# 6_upstream_con.net
KiCad netlist of a schematic drawn in Altium Designer
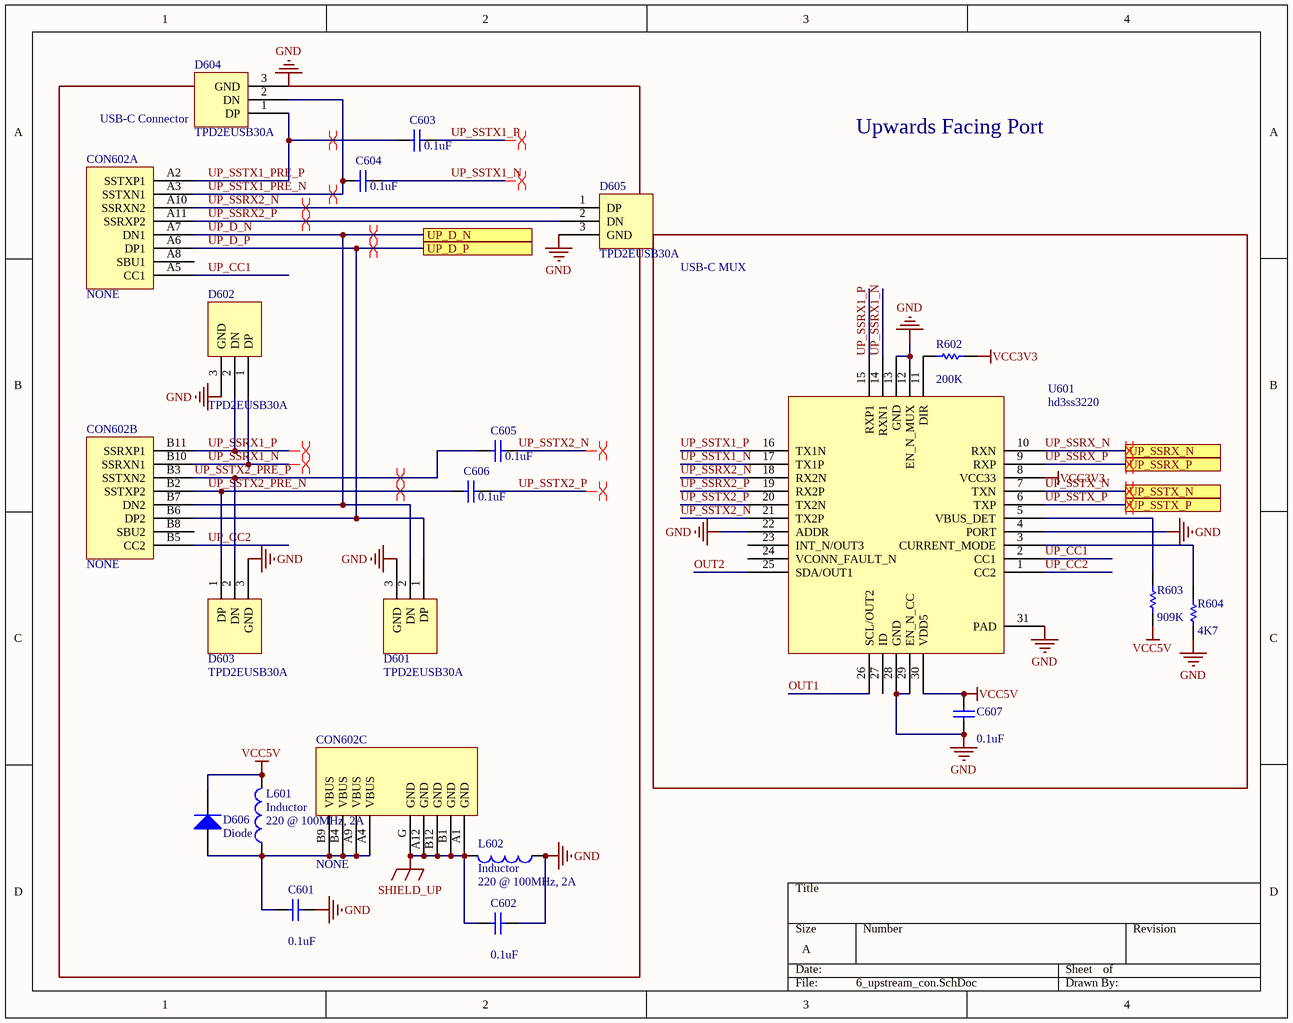
[diagram p0: 6_upstream_con.SchDoc]

(export (version "E")
  (design (tool "Eeschema 10.0.6"))
  (components
    (comp (ref "C601")
      (value "0.1uF")
      (footprint "C0603[1608]")
      (description "Capacitor")
      (fields (field (name "MFG") "KEMET") (field (name "LCSC PART #") "C14663"))
      (libsource (lib "Miscellaneous Devices") (part "Cap"))
    )
    (comp (ref "C602")
      (value "0.1uF")
      (footprint "C0603[1608]")
      (description "Capacitor")
      (fields (field (name "MFG") "KEMET") (field (name "LCSC PART #") "C14663"))
      (libsource (lib "Miscellaneous Devices") (part "Cap"))
    )
    (comp (ref "C603")
      (value "0.1uF")
      (footprint "C0402[1005]")
      (description "Capacitor")
      (fields (field (name "MFG") "KEMET") (field (name "LCSC PART #") "C1525"))
      (libsource (lib "Miscellaneous Devices") (part "Cap"))
    )
    (comp (ref "C604")
      (value "0.1uF")
      (footprint "C0402[1005]")
      (description "Capacitor")
      (fields (field (name "MFG") "KEMET") (field (name "LCSC PART #") "C1525"))
      (libsource (lib "Miscellaneous Devices") (part "Cap"))
    )
    (comp (ref "C605")
      (value "0.1uF")
      (footprint "C0402[1005]")
      (description "Capacitor")
      (fields (field (name "MFG") "KEMET") (field (name "LCSC PART #") "C1525"))
      (libsource (lib "Miscellaneous Devices") (part "Cap"))
    )
    (comp (ref "C606")
      (value "0.1uF")
      (footprint "C0402[1005]")
      (description "Capacitor")
      (fields (field (name "MFG") "KEMET") (field (name "LCSC PART #") "C1525"))
      (libsource (lib "Miscellaneous Devices") (part "Cap"))
    )
    (comp (ref "C607")
      (value "0.1uF")
      (footprint "C0603[1608]")
      (description "Capacitor")
      (fields (field (name "MFG") "KEMET") (field (name "LCSC PART #") "C14663"))
      (libsource (lib "Miscellaneous Devices") (part "Cap"))
    )
    (comp (ref "CON602")
      (value "for up to 1.6mm pcb")
      (footprint "XKB USB-C u262-241n-4bv64")
      (fields
        (field (name "JLC") "NONE")
        (field (name "LCSC PART #") "C388660")
        (field (name "MRF.PART") "U262-241N-4BV64")
      )
      (libsource (lib "") (part "XKB USB-C u262-241n-4bv64_1"))
    )
    (comp (ref "D601")
      (value "TPD2EUSB30A")
      (footprint "TPD2EUSB30A")
      (fields
        (field (name "MFG") "Texas Instruments")
        (field (name "LCSC PART #") "C94934")
        (field (name "MRF.PART") "TPD2EUSB30ADRTR")
      )
      (libsource (lib "") (part "TPD2EUSB30A_2"))
    )
    (comp (ref "D602")
      (value "TPD2EUSB30A")
      (footprint "TPD2EUSB30A")
      (fields
        (field (name "MFG") "Texas Instruments")
        (field (name "LCSC PART #") "C94934")
        (field (name "MRF.PART") "TPD2EUSB30ADRTR")
      )
      (libsource (lib "lib") (part "TPD2EUSB30A"))
    )
    (comp (ref "D603")
      (value "TPD2EUSB30A")
      (footprint "TPD2EUSB30A")
      (fields
        (field (name "MFG") "Texas Instruments")
        (field (name "LCSC PART #") "C94934")
        (field (name "MRF.PART") "TPD2EUSB30ADRTR")
      )
      (libsource (lib "") (part "TPD2EUSB30A_1"))
    )
    (comp (ref "D604")
      (value "TPD2EUSB30A")
      (footprint "TPD2EUSB30A")
      (fields
        (field (name "MFG") "Texas Instruments")
        (field (name "LCSC PART #") "C94934")
        (field (name "MRF.PART") "TPD2EUSB30ADRTR")
      )
      (libsource (lib "") (part "TPD2EUSB30A_1"))
    )
    (comp (ref "D605")
      (value "TPD2EUSB30A")
      (footprint "TPD2EUSB30A")
      (fields
        (field (name "MFG") "Texas Instruments")
        (field (name "LCSC PART #") "C94934")
        (field (name "MRF.PART") "TPD2EUSB30ADRTR")
      )
      (libsource (lib "lib") (part "TPD2EUSB30A"))
    )
    (comp (ref "D606")
      (value "Diode")
      (footprint "LED0603[1608]")
      (description "Default Diode")
      (fields (field (name "MFG") "Comchip Technology"))
      (libsource (lib "Miscellaneous Devices") (part "Diode"))
    )
    (comp (ref "L601")
      (value "Inductor")
      (footprint "L0603[1608]")
      (fields
        (field (name "ALTIUM_VALUE") "220 @ 100MHz, 2A")
        (field (name "MFG") "Murata Electronics North America")
        (field (name "LCSC PART #") "C85832")
        (field (name "MRF.PART") "BLM18KG331SN1D")
      )
      (libsource (lib "Miscellaneous Devices") (part "Inductor"))
    )
    (comp (ref "L602")
      (value "Inductor")
      (footprint "L0603[1608]")
      (fields
        (field (name "ALTIUM_VALUE") "220 @ 100MHz, 2A")
        (field (name "MFG") "Murata Electronics North America")
        (field (name "LCSC PART #") "C85832")
        (field (name "MRF.PART") "BLM18KG331SN1D")
      )
      (libsource (lib "Miscellaneous Devices") (part "Inductor"))
    )
    (comp (ref "R602")
      (value "200K")
      (footprint "R0603[1608]")
      (description "Resistor")
      (fields (field (name "MFG") "Vishay Dale") (field (name "LCSC PART #") "C25811"))
      (libsource (lib "Miscellaneous Devices") (part "Res1"))
    )
    (comp (ref "R603")
      (value "909K")
      (footprint "R0603[1608]")
      (description "Resistor")
      (fields (field (name "MFG") "Vishay Dale") (field (name "LCSC PART #") "C22935"))
      (libsource (lib "Miscellaneous Devices") (part "Res1"))
    )
    (comp (ref "R604")
      (value "4K7")
      (footprint "R0603[1608]")
      (description "Resistor")
      (fields (field (name "MFG") "Vishay Dale") (field (name "LCSC PART #") "C23162"))
      (libsource (lib "Miscellaneous Devices") (part "Res1"))
    )
    (comp (ref "U601")
      (value "hd3ss3220")
      (footprint "hd3ss3220")
      (fields
        (field (name "MFG") "Texas Instruments")
        (field (name "LCSC PART #") "C165155")
        (field (name "MRF.PART") "HD3SS3220RNHR")
      )
      (libsource (lib "lib") (part "hd3ss3220"))
    )
  )
  (nets
    (net (code "1") (name "/OUT1") (class "Default")
      (node (ref "U601") (pin "26") (pinfunction "SCL/OUT2_26") (pintype "passive"))
    )
    (net (code "2") (name "/OUT2") (class "Default")
      (node (ref "U601") (pin "25") (pinfunction "SDA/OUT1_25") (pintype "passive"))
    )
    (net (code "3") (name "/UP_CC1") (class "Default")
      (node (ref "CON602") (pin "A5") (pinfunction "CC1_A5") (pintype "passive"))
      (node (ref "U601") (pin "2") (pinfunction "CC1_2") (pintype "passive"))
    )
    (net (code "4") (name "/UP_CC2") (class "Default")
      (node (ref "CON602") (pin "B5") (pinfunction "CC2_B5") (pintype "passive"))
      (node (ref "U601") (pin "1") (pinfunction "CC2_1") (pintype "passive"))
    )
    (net (code "5") (name "/UP_D_N") (class "Default")
      (node (ref "CON602") (pin "A7") (pinfunction "DN1_A7") (pintype "passive"))
      (node (ref "CON602") (pin "B7") (pinfunction "DN2_B7") (pintype "passive"))
      (node (ref "D601") (pin "2") (pinfunction "DN_2") (pintype "passive"))
    )
    (net (code "6") (name "/UP_D_P") (class "Default")
      (node (ref "CON602") (pin "A6") (pinfunction "DP1_A6") (pintype "passive"))
      (node (ref "CON602") (pin "B6") (pinfunction "DP2_B6") (pintype "passive"))
      (node (ref "D601") (pin "1") (pinfunction "DP_1") (pintype "passive"))
    )
    (net (code "7") (name "/UP_SSRX1_N") (class "Default")
      (node (ref "CON602") (pin "B10") (pinfunction "SSRXN1_B10") (pintype "passive"))
      (node (ref "D602") (pin "1") (pinfunction "DP_1") (pintype "passive"))
      (node (ref "U601") (pin "14") (pinfunction "RXN1_14") (pintype "passive"))
    )
    (net (code "8") (name "/UP_SSRX1_P") (class "Default")
      (node (ref "CON602") (pin "B11") (pinfunction "SSRXP1_B11") (pintype "passive"))
      (node (ref "D602") (pin "2") (pinfunction "DN_2") (pintype "passive"))
      (node (ref "U601") (pin "15") (pinfunction "RXP1_15") (pintype "passive"))
    )
    (net (code "9") (name "/UP_SSRX2_N") (class "Default")
      (node (ref "CON602") (pin "A10") (pinfunction "SSRXN2_A10") (pintype "passive"))
      (node (ref "D605") (pin "1") (pinfunction "DP_1") (pintype "passive"))
      (node (ref "U601") (pin "18") (pinfunction "RX2N_18") (pintype "passive"))
    )
    (net (code "10") (name "/UP_SSRX2_P") (class "Default")
      (node (ref "CON602") (pin "A11") (pinfunction "SSRXP2_A11") (pintype "passive"))
      (node (ref "D605") (pin "2") (pinfunction "DN_2") (pintype "passive"))
      (node (ref "U601") (pin "19") (pinfunction "RX2P_19") (pintype "passive"))
    )
    (net (code "11") (name "/UP_SSRX_N") (class "Default")
      (node (ref "U601") (pin "10") (pinfunction "RXN_10") (pintype "passive"))
    )
    (net (code "12") (name "/UP_SSRX_P") (class "Default")
      (node (ref "U601") (pin "9") (pinfunction "RXP_9") (pintype "passive"))
    )
    (net (code "13") (name "/UP_SSTX1_N") (class "Default")
      (node (ref "C604") (pin "2") (pinfunction "2_2") (pintype "passive"))
      (node (ref "U601") (pin "17") (pinfunction "TX1P_17") (pintype "passive"))
    )
    (net (code "14") (name "/UP_SSTX1_P") (class "Default")
      (node (ref "C603") (pin "2") (pinfunction "2_2") (pintype "passive"))
      (node (ref "U601") (pin "16") (pinfunction "TX1N_16") (pintype "passive"))
    )
    (net (code "15") (name "/UP_SSTX1_PRE_N") (class "Default")
      (node (ref "C604") (pin "1") (pinfunction "1_1") (pintype "passive"))
      (node (ref "CON602") (pin "A3") (pinfunction "SSTXN1_A3") (pintype "passive"))
      (node (ref "D604") (pin "2") (pinfunction "DN_2") (pintype "passive"))
    )
    (net (code "16") (name "/UP_SSTX1_PRE_P") (class "Default")
      (node (ref "C603") (pin "1") (pinfunction "1_1") (pintype "passive"))
      (node (ref "CON602") (pin "A2") (pinfunction "SSTXP1_A2") (pintype "passive"))
      (node (ref "D604") (pin "1") (pinfunction "DP_1") (pintype "passive"))
    )
    (net (code "17") (name "/UP_SSTX2_N") (class "Default")
      (node (ref "C605") (pin "2") (pinfunction "2_2") (pintype "passive"))
      (node (ref "U601") (pin "21") (pinfunction "TX2P_21") (pintype "passive"))
    )
    (net (code "18") (name "/UP_SSTX2_P") (class "Default")
      (node (ref "C606") (pin "2") (pinfunction "2_2") (pintype "passive"))
      (node (ref "U601") (pin "20") (pinfunction "TX2N_20") (pintype "passive"))
    )
    (net (code "19") (name "/UP_SSTX2_PRE_N") (class "Default")
      (node (ref "C606") (pin "1") (pinfunction "1_1") (pintype "passive"))
      (node (ref "CON602") (pin "B2") (pinfunction "SSTXP2_B2") (pintype "passive"))
      (node (ref "D603") (pin "1") (pinfunction "DP_1") (pintype "passive"))
    )
    (net (code "20") (name "/UP_SSTX2_PRE_P") (class "Default")
      (node (ref "C605") (pin "1") (pinfunction "1_1") (pintype "passive"))
      (node (ref "CON602") (pin "B3") (pinfunction "SSTXN2_B3") (pintype "passive"))
      (node (ref "D603") (pin "2") (pinfunction "DN_2") (pintype "passive"))
    )
    (net (code "21") (name "/UP_SSTX_N") (class "Default")
      (node (ref "U601") (pin "7") (pinfunction "TXN_7") (pintype "passive"))
    )
    (net (code "22") (name "/UP_SSTX_P") (class "Default")
      (node (ref "U601") (pin "6") (pinfunction "TXP_6") (pintype "passive"))
    )
    (net (code "23") (name "GND") (class "Default")
      (node (ref "C601") (pin "1") (pinfunction "1_1") (pintype "passive"))
      (node (ref "C602") (pin "1") (pinfunction "1_1") (pintype "passive"))
      (node (ref "C607") (pin "1") (pinfunction "1_1") (pintype "passive"))
      (node (ref "D601") (pin "3") (pinfunction "GND_3") (pintype "passive"))
      (node (ref "D602") (pin "3") (pinfunction "GND_3") (pintype "passive"))
      (node (ref "D603") (pin "3") (pinfunction "GND_3") (pintype "passive"))
      (node (ref "D604") (pin "3") (pinfunction "GND_3") (pintype "passive"))
      (node (ref "D605") (pin "3") (pinfunction "GND_3") (pintype "passive"))
      (node (ref "L602") (pin "1") (pinfunction "1_1") (pintype "passive"))
      (node (ref "R604") (pin "2") (pinfunction "2_2") (pintype "passive"))
      (node (ref "U601") (pin "12") (pinfunction "EN_N_MUX_12") (pintype "passive"))
      (node (ref "U601") (pin "13") (pinfunction "GND_13") (pintype "passive"))
      (node (ref "U601") (pin "22") (pinfunction "ADDR_22") (pintype "passive"))
      (node (ref "U601") (pin "28") (pinfunction "GND_28") (pintype "passive"))
      (node (ref "U601") (pin "29") (pinfunction "EN_N_CC_29") (pintype "passive"))
      (node (ref "U601") (pin "31") (pinfunction "PAD_31") (pintype "passive"))
      (node (ref "U601") (pin "4") (pinfunction "PORT_4") (pintype "passive"))
    )
    (net (code "24") (name "Net-(D606-A)") (class "Default")
      (node (ref "C601") (pin "2") (pinfunction "2_2") (pintype "passive"))
      (node (ref "CON602") (pin "A4") (pinfunction "VBUS_A4") (pintype "passive"))
      (node (ref "CON602") (pin "A9") (pinfunction "VBUS_A9") (pintype "passive"))
      (node (ref "CON602") (pin "B4") (pinfunction "VBUS_B4") (pintype "passive"))
      (node (ref "CON602") (pin "B9") (pinfunction "VBUS_B9") (pintype "passive"))
      (node (ref "D606") (pin "1") (pinfunction "A_1") (pintype "passive"))
      (node (ref "L601") (pin "1") (pinfunction "1_1") (pintype "passive"))
    )
    (net (code "25") (name "Net-(U601-CURRENT_MODE)") (class "Default")
      (node (ref "R604") (pin "1") (pinfunction "1_1") (pintype "passive"))
      (node (ref "U601") (pin "3") (pinfunction "CURRENT_MODE_3") (pintype "passive"))
    )
    (net (code "26") (name "Net-(U601-DIR)") (class "Default")
      (node (ref "R602") (pin "1") (pinfunction "1_1") (pintype "passive"))
      (node (ref "U601") (pin "11") (pinfunction "DIR_11") (pintype "passive"))
    )
    (net (code "27") (name "Net-(U601-VBUS_DET)") (class "Default")
      (node (ref "R603") (pin "1") (pinfunction "1_1") (pintype "passive"))
      (node (ref "U601") (pin "5") (pinfunction "VBUS_DET_5") (pintype "passive"))
    )
    (net (code "28") (name "SHIELD_UP") (class "Default")
      (node (ref "C602") (pin "2") (pinfunction "2_2") (pintype "passive"))
      (node (ref "CON602") (pin "A1") (pinfunction "GND_A1") (pintype "passive"))
      (node (ref "CON602") (pin "A12") (pinfunction "GND_A12") (pintype "passive"))
      (node (ref "CON602") (pin "B1") (pinfunction "GND_B1") (pintype "passive"))
      (node (ref "CON602") (pin "B12") (pinfunction "GND_B12") (pintype "passive"))
      (node (ref "CON602") (pin "G") (pinfunction "GND_G") (pintype "passive"))
      (node (ref "L602") (pin "2") (pinfunction "2_2") (pintype "passive"))
    )
    (net (code "29") (name "VCC3V3") (class "Default")
      (node (ref "R602") (pin "2") (pinfunction "2_2") (pintype "passive"))
      (node (ref "U601") (pin "8") (pinfunction "VCC33_8") (pintype "passive"))
    )
    (net (code "30") (name "VCC5V") (class "Default")
      (node (ref "C607") (pin "2") (pinfunction "2_2") (pintype "passive"))
      (node (ref "D606") (pin "2") (pinfunction "K_2") (pintype "passive"))
      (node (ref "L601") (pin "2") (pinfunction "2_2") (pintype "passive"))
      (node (ref "R603") (pin "2") (pinfunction "2_2") (pintype "passive"))
      (node (ref "U601") (pin "30") (pinfunction "VDD5_30") (pintype "passive"))
    )
    (net (code "31") (name "unconnected-(CON602A-SBU1-PadA8)") (class "Default")
      (node (ref "CON602") (pin "A8") (pinfunction "SBU1_A8") (pintype "passive"))
    )
    (net (code "32") (name "unconnected-(CON602B-SBU2-PadB8)") (class "Default")
      (node (ref "CON602") (pin "B8") (pinfunction "SBU2_B8") (pintype "passive"))
    )
    (net (code "33") (name "unconnected-(U601-ID-Pad27)") (class "Default")
      (node (ref "U601") (pin "27") (pinfunction "ID_27") (pintype "passive"))
    )
    (net (code "34") (name "unconnected-(U601-INT_N{slash}OUT3-Pad23)") (class "Default")
      (node (ref "U601") (pin "23") (pinfunction "INT_N/OUT3_23") (pintype "passive"))
    )
    (net (code "35") (name "unconnected-(U601-VCONN_FAULT_N-Pad24)") (class "Default")
      (node (ref "U601") (pin "24") (pinfunction "VCONN_FAULT_N_24") (pintype "passive"))
    )
  )
)
